# xx_backplane_shield_xi.net
KiCad netlist of a schematic drawn in EAGLE
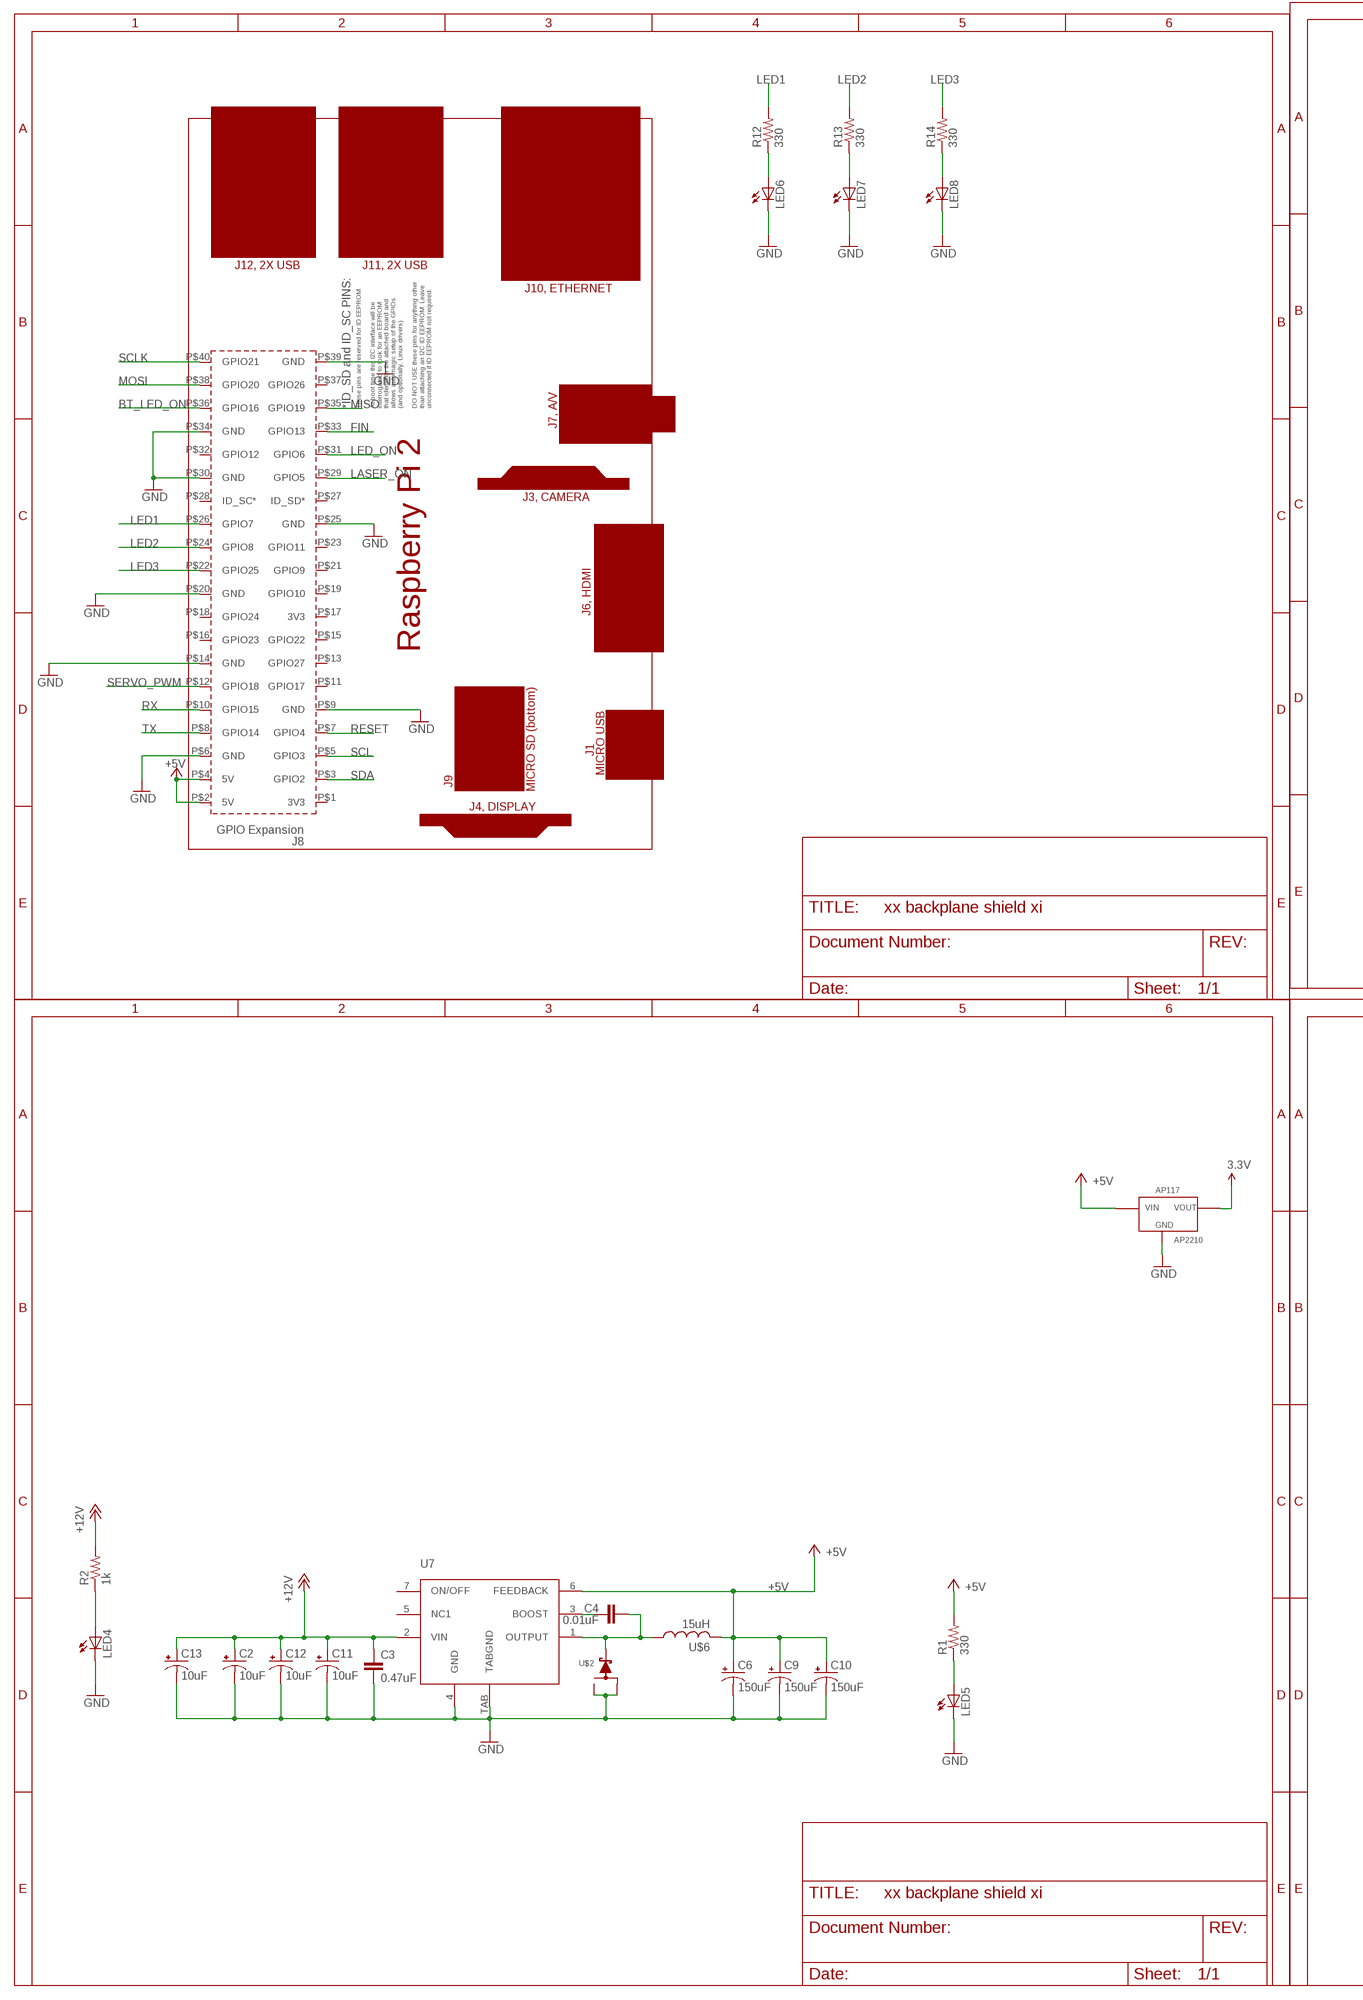
[diagram p0: schematic, sheet 1, part 1 of 2]
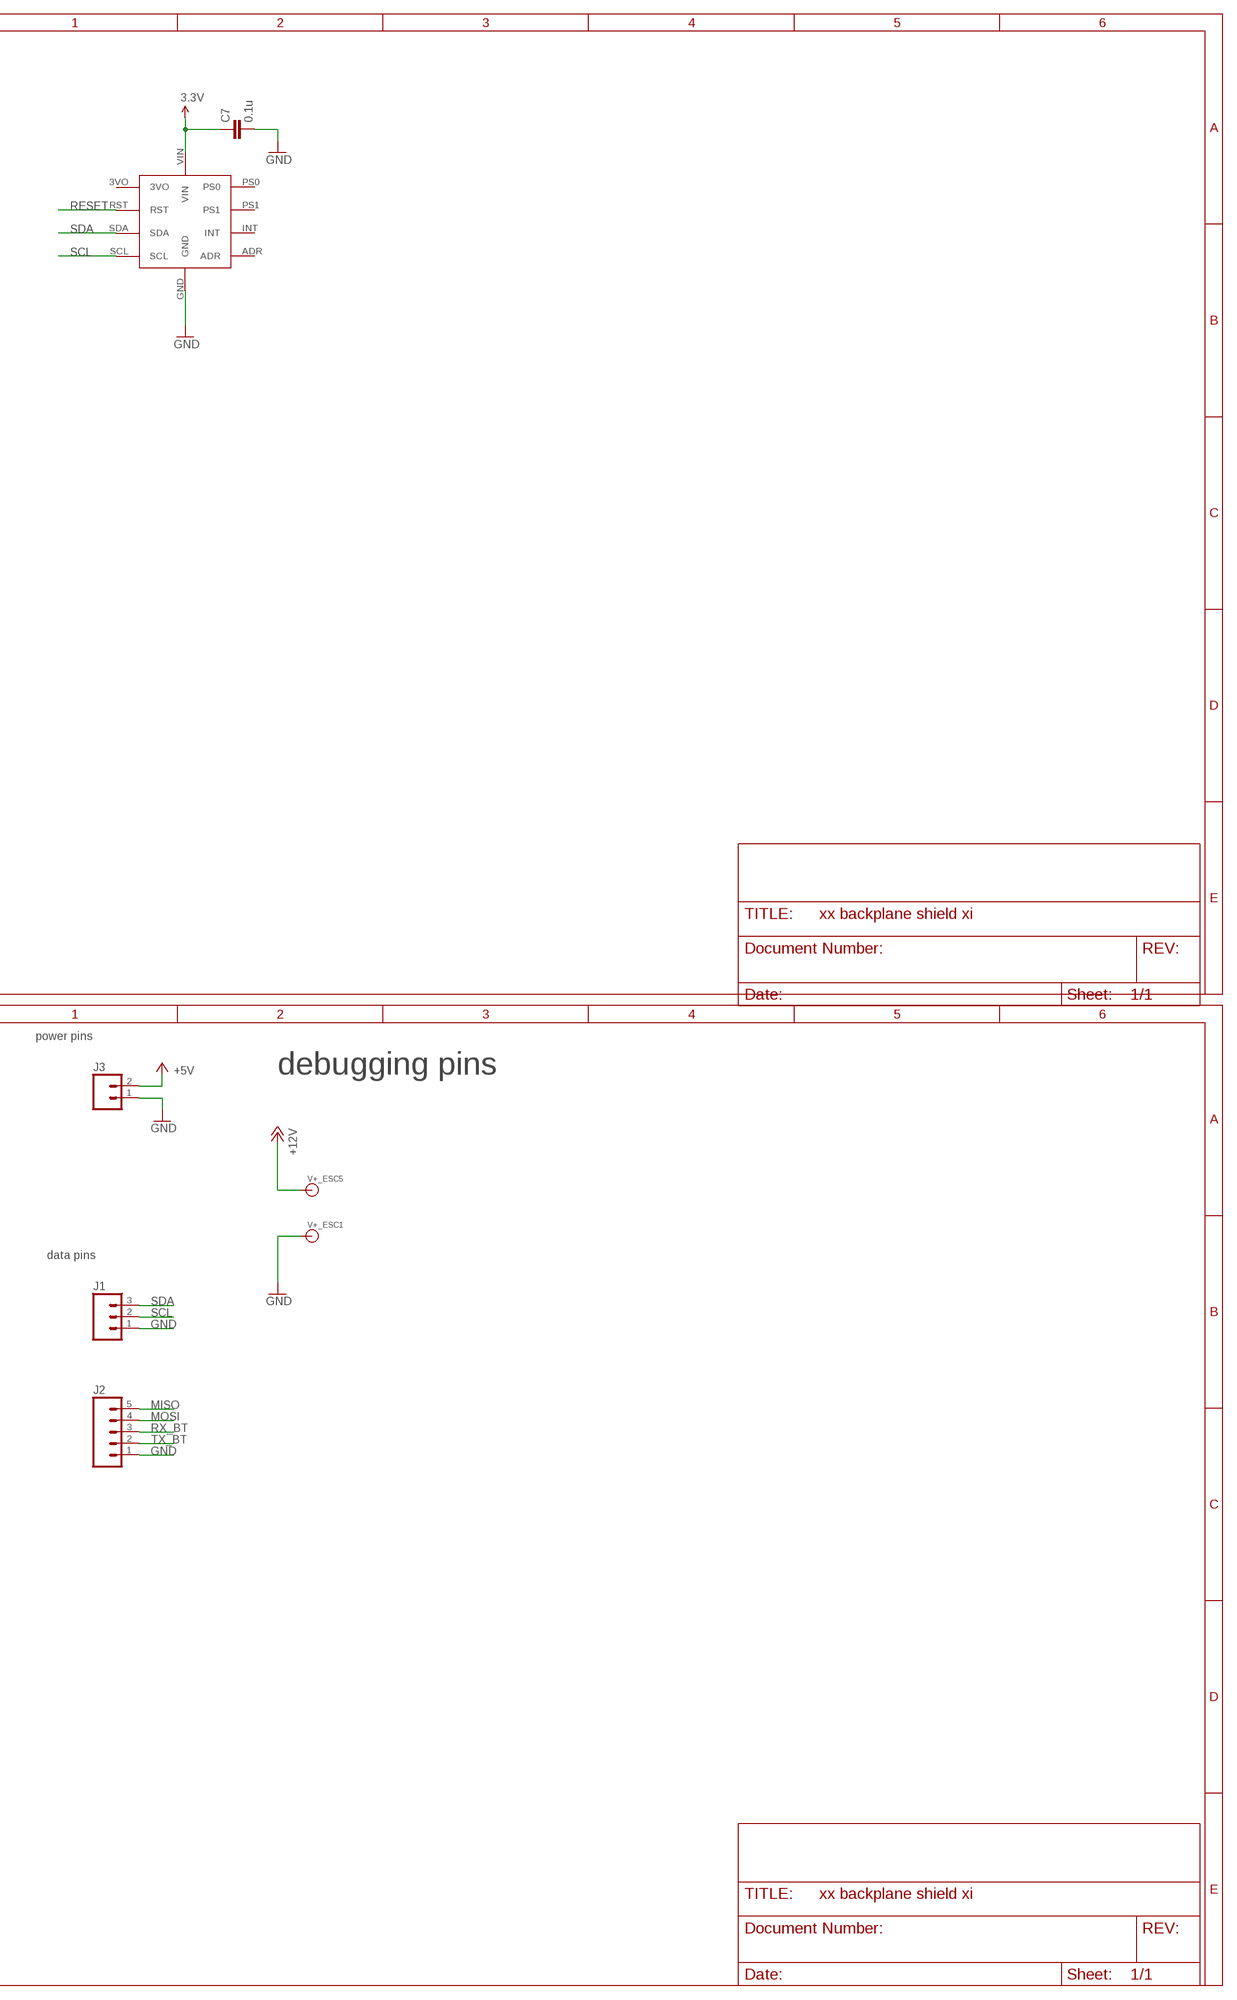
[diagram p1: schematic, sheet 1, part 2 of 2]

(export (version "E")
  (design (tool "Eeschema 10.0.6"))
  (components
    (comp (ref "C2")
      (value "10uF")
      (footprint "eagle-import:CTAN(7.30_4.30MM)")
      (libsource (lib "eagle-import") (part "C-TANTALUM(10UF_150UF)"))
    )
    (comp (ref "C3")
      (value "0.47uF")
      (footprint "eagle-import:0603")
      (libsource (lib "eagle-import") (part "0.18UF-0603-10V-10%"))
    )
    (comp (ref "C4")
      (value "0.01uF")
      (footprint "eagle-import:0603-CAP")
      (libsource (lib "eagle-import") (part "CAP0603-CAP"))
    )
    (comp (ref "C6")
      (value "150uF")
      (footprint "eagle-import:CTAN(7.30_4.30MM)")
      (libsource (lib "eagle-import") (part "C-TANTALUM(10UF_150UF)"))
    )
    (comp (ref "C7")
      (value "0.1u")
      (footprint "eagle-import:0603-CAP")
      (libsource (lib "eagle-import") (part "CAP0603-CAP"))
    )
    (comp (ref "C9")
      (value "150uF")
      (footprint "eagle-import:CTAN(7.30_4.30MM)")
      (libsource (lib "eagle-import") (part "C-TANTALUM(10UF_150UF)"))
    )
    (comp (ref "C10")
      (value "150uF")
      (footprint "eagle-import:CTAN(7.30_4.30MM)")
      (libsource (lib "eagle-import") (part "C-TANTALUM(10UF_150UF)"))
    )
    (comp (ref "C11")
      (value "10uF")
      (footprint "eagle-import:CTAN(7.30_4.30MM)")
      (libsource (lib "eagle-import") (part "C-TANTALUM(10UF_150UF)"))
    )
    (comp (ref "C12")
      (value "10uF")
      (footprint "eagle-import:CTAN(7.30_4.30MM)")
      (libsource (lib "eagle-import") (part "C-TANTALUM(10UF_150UF)"))
    )
    (comp (ref "C13")
      (value "10uF")
      (footprint "eagle-import:CTAN(7.30_4.30MM)")
      (libsource (lib "eagle-import") (part "C-TANTALUM(10UF_150UF)"))
    )
    (comp (ref "J1")
      (value "M03PTH")
      (footprint "eagle-import:1X03")
      (libsource (lib "eagle-import") (part "M03PTH"))
    )
    (comp (ref "J2")
      (value "M05PTH")
      (footprint "eagle-import:1X05")
      (libsource (lib "eagle-import") (part "M05PTH"))
    )
    (comp (ref "J3")
      (value "M02PTH")
      (footprint "eagle-import:1X02")
      (libsource (lib "eagle-import") (part "M02PTH"))
    )
    (comp (ref "LED4")
      (value "LEDSML0603")
      (footprint "eagle-import:SML0603")
      (libsource (lib "eagle-import") (part "LEDSML0603"))
    )
    (comp (ref "LED5")
      (value "LEDSML0603")
      (footprint "eagle-import:SML0603")
      (libsource (lib "eagle-import") (part "LEDSML0603"))
    )
    (comp (ref "LED6")
      (value "LEDSML0603")
      (footprint "eagle-import:SML0603")
      (libsource (lib "eagle-import") (part "LEDSML0603"))
    )
    (comp (ref "LED7")
      (value "LEDSML0603")
      (footprint "eagle-import:SML0603")
      (libsource (lib "eagle-import") (part "LEDSML0603"))
    )
    (comp (ref "LED8")
      (value "LEDSML0603")
      (footprint "eagle-import:SML0603")
      (libsource (lib "eagle-import") (part "LEDSML0603"))
    )
    (comp (ref "PCB1")
      (value "RPI2")
      (footprint "eagle-import:RPI2")
      (libsource (lib "eagle-import") (part "RPI2"))
    )
    (comp (ref "R1")
      (value "330")
      (footprint "eagle-import:R0603")
      (libsource (lib "eagle-import") (part "R-US_R0603"))
    )
    (comp (ref "R2")
      (value "1k")
      (footprint "eagle-import:R0603")
      (libsource (lib "eagle-import") (part "R-US_R0603"))
    )
    (comp (ref "R12")
      (value "330")
      (footprint "eagle-import:R0603")
      (libsource (lib "eagle-import") (part "R-US_R0603"))
    )
    (comp (ref "R13")
      (value "330")
      (footprint "eagle-import:R0603")
      (libsource (lib "eagle-import") (part "R-US_R0603"))
    )
    (comp (ref "R14")
      (value "330")
      (footprint "eagle-import:R0603")
      (libsource (lib "eagle-import") (part "R-US_R0603"))
    )
    (comp (ref "U$2")
      (value "SWITCHMODE_SCHOTTKY")
      (footprint "eagle-import:DPAK-3")
      (libsource (lib "eagle-import") (part "SWITCHMODE_SCHOTTKY"))
    )
    (comp (ref "U$3")
      (value "BNO055_9DOF_BREAKOUT")
      (footprint "eagle-import:BNO055")
      (libsource (lib "eagle-import") (part "BNO055_9DOF_BREAKOUT"))
    )
    (comp (ref "U$5")
      (value "AP2210")
      (footprint "eagle-import:SOT-23-3")
      (libsource (lib "eagle-import") (part "AP2210"))
    )
    (comp (ref "U$6")
      (value "15uH")
      (footprint "eagle-import:HCMA1305")
      (libsource (lib "eagle-import") (part "HCMA1305"))
    )
    (comp (ref "U7")
      (value "LM2678")
      (footprint "eagle-import:LM2678")
      (libsource (lib "eagle-import") (part "LM2678"))
    )
    (comp (ref "V+_ESC1")
      (value "BANANA_CONN")
      (footprint "eagle-import:BANANA_CONN")
      (libsource (lib "eagle-import") (part "BANANA_CONN"))
    )
    (comp (ref "V+_ESC5")
      (value "BANANA_CONN")
      (footprint "eagle-import:BANANA_CONN")
      (libsource (lib "eagle-import") (part "BANANA_CONN"))
    )
  )
  (nets
    (net (code "1") (name "+5V") (class "Default")
      (node (ref "C10") (pin "+") (pinfunction "+_+") (pintype "passive"))
      (node (ref "C6") (pin "+") (pinfunction "+_+") (pintype "passive"))
      (node (ref "C9") (pin "+") (pinfunction "+_+") (pintype "passive"))
      (node (ref "J3") (pin "2") (pinfunction "2_2") (pintype "passive"))
      (node (ref "PCB1") (pin "P$2") (pinfunction "5V_P$2") (pintype "bidirectional"))
      (node (ref "PCB1") (pin "P$4") (pinfunction "5V_P$4") (pintype "bidirectional"))
      (node (ref "R1") (pin "2") (pinfunction "2_2") (pintype "passive"))
      (node (ref "U$5") (pin "VIN") (pinfunction "VIN_VIN") (pintype "input"))
      (node (ref "U$6") (pin "P$2") (pinfunction "2_P$2") (pintype "passive"))
      (node (ref "U7") (pin "6") (pinfunction "FEEDBACK_6") (pintype "bidirectional"))
    )
    (net (code "2") (name "+12V") (class "Default")
      (node (ref "C11") (pin "+") (pinfunction "+_+") (pintype "passive"))
      (node (ref "C12") (pin "+") (pinfunction "+_+") (pintype "passive"))
      (node (ref "C13") (pin "+") (pinfunction "+_+") (pintype "passive"))
      (node (ref "C2") (pin "+") (pinfunction "+_+") (pintype "passive"))
      (node (ref "C3") (pin "1") (pinfunction "1_1") (pintype "passive"))
      (node (ref "R2") (pin "2") (pinfunction "2_2") (pintype "passive"))
      (node (ref "U7") (pin "2") (pinfunction "VIN_2") (pintype "bidirectional"))
      (node (ref "V+_ESC5") (pin "P$1") (pinfunction "1_P$1") (pintype "passive"))
    )
    (net (code "3") (name "/BT_LED_ON") (class "Default")
      (node (ref "PCB1") (pin "P$36") (pinfunction "GPIO16_P$36") (pintype "bidirectional"))
    )
    (net (code "4") (name "/FIN") (class "Default")
      (node (ref "PCB1") (pin "P$33") (pinfunction "GPIO13_P$33") (pintype "bidirectional"))
    )
    (net (code "5") (name "/LASER_ON") (class "Default")
      (node (ref "PCB1") (pin "P$29") (pinfunction "GPIO5_P$29") (pintype "bidirectional"))
    )
    (net (code "6") (name "/LED1") (class "Default")
      (node (ref "PCB1") (pin "P$26") (pinfunction "GPIO7_P$26") (pintype "bidirectional"))
      (node (ref "R12") (pin "2") (pinfunction "2_2") (pintype "passive"))
    )
    (net (code "7") (name "/LED2") (class "Default")
      (node (ref "PCB1") (pin "P$24") (pinfunction "GPIO8_P$24") (pintype "bidirectional"))
      (node (ref "R13") (pin "2") (pinfunction "2_2") (pintype "passive"))
    )
    (net (code "8") (name "/LED3") (class "Default")
      (node (ref "PCB1") (pin "P$22") (pinfunction "GPIO25_P$22") (pintype "bidirectional"))
      (node (ref "R14") (pin "2") (pinfunction "2_2") (pintype "passive"))
    )
    (net (code "9") (name "/LED_ON") (class "Default")
      (node (ref "PCB1") (pin "P$31") (pinfunction "GPIO6_P$31") (pintype "bidirectional"))
    )
    (net (code "10") (name "/MISO") (class "Default")
      (node (ref "J2") (pin "5") (pinfunction "5_5") (pintype "passive"))
      (node (ref "PCB1") (pin "P$35") (pinfunction "GPIO19_P$35") (pintype "bidirectional"))
    )
    (net (code "11") (name "/MOSI") (class "Default")
      (node (ref "J2") (pin "4") (pinfunction "4_4") (pintype "passive"))
      (node (ref "PCB1") (pin "P$38") (pinfunction "GPIO20_P$38") (pintype "bidirectional"))
    )
    (net (code "12") (name "/RESET") (class "Default")
      (node (ref "PCB1") (pin "P$7") (pinfunction "GPIO4_P$7") (pintype "bidirectional"))
      (node (ref "U$3") (pin "RST") (pinfunction "RST_RST") (pintype "bidirectional"))
    )
    (net (code "13") (name "/RX") (class "Default")
      (node (ref "PCB1") (pin "P$10") (pinfunction "GPIO15_P$10") (pintype "bidirectional"))
    )
    (net (code "14") (name "/RX_BT") (class "Default")
      (node (ref "J2") (pin "3") (pinfunction "3_3") (pintype "passive"))
    )
    (net (code "15") (name "/SCL") (class "Default")
      (node (ref "J1") (pin "2") (pinfunction "2_2") (pintype "passive"))
      (node (ref "PCB1") (pin "P$5") (pinfunction "GPIO3_P$5") (pintype "bidirectional"))
      (node (ref "U$3") (pin "SCL") (pinfunction "SCL_SCL") (pintype "bidirectional"))
    )
    (net (code "16") (name "/SCLK") (class "Default")
      (node (ref "PCB1") (pin "P$40") (pinfunction "GPIO21_P$40") (pintype "bidirectional"))
    )
    (net (code "17") (name "/SDA") (class "Default")
      (node (ref "J1") (pin "3") (pinfunction "3_3") (pintype "passive"))
      (node (ref "PCB1") (pin "P$3") (pinfunction "GPIO2_P$3") (pintype "bidirectional"))
      (node (ref "U$3") (pin "SDA") (pinfunction "SDA_SDA") (pintype "bidirectional"))
    )
    (net (code "18") (name "/SERVO_PWM") (class "Default")
      (node (ref "PCB1") (pin "P$12") (pinfunction "GPIO18_P$12") (pintype "bidirectional"))
    )
    (net (code "19") (name "/TX") (class "Default")
      (node (ref "PCB1") (pin "P$8") (pinfunction "GPIO14_P$8") (pintype "bidirectional"))
    )
    (net (code "20") (name "/TX_BT") (class "Default")
      (node (ref "J2") (pin "2") (pinfunction "2_2") (pintype "passive"))
    )
    (net (code "21") (name "3.3V") (class "Default")
      (node (ref "C7") (pin "1") (pinfunction "1_1") (pintype "passive"))
      (node (ref "U$3") (pin "VIN") (pinfunction "VIN_VIN") (pintype "bidirectional"))
      (node (ref "U$5") (pin "VOUT") (pinfunction "VOUT_VOUT") (pintype "output"))
    )
    (net (code "22") (name "GND") (class "Default")
      (node (ref "C10") (pin "-") (pinfunction "-_-") (pintype "passive"))
      (node (ref "C11") (pin "-") (pinfunction "-_-") (pintype "passive"))
      (node (ref "C12") (pin "-") (pinfunction "-_-") (pintype "passive"))
      (node (ref "C13") (pin "-") (pinfunction "-_-") (pintype "passive"))
      (node (ref "C2") (pin "-") (pinfunction "-_-") (pintype "passive"))
      (node (ref "C3") (pin "2") (pinfunction "2_2") (pintype "passive"))
      (node (ref "C6") (pin "-") (pinfunction "-_-") (pintype "passive"))
      (node (ref "C7") (pin "2") (pinfunction "2_2") (pintype "passive"))
      (node (ref "C9") (pin "-") (pinfunction "-_-") (pintype "passive"))
      (node (ref "J1") (pin "1") (pinfunction "1_1") (pintype "passive"))
      (node (ref "J2") (pin "1") (pinfunction "1_1") (pintype "passive"))
      (node (ref "J3") (pin "1") (pinfunction "1_1") (pintype "passive"))
      (node (ref "LED4") (pin "C") (pinfunction "C_C") (pintype "passive"))
      (node (ref "LED5") (pin "C") (pinfunction "C_C") (pintype "passive"))
      (node (ref "LED6") (pin "C") (pinfunction "C_C") (pintype "passive"))
      (node (ref "LED7") (pin "C") (pinfunction "C_C") (pintype "passive"))
      (node (ref "LED8") (pin "C") (pinfunction "C_C") (pintype "passive"))
      (node (ref "PCB1") (pin "P$14") (pinfunction "GND_P$14") (pintype "bidirectional"))
      (node (ref "PCB1") (pin "P$20") (pinfunction "GND_P$20") (pintype "bidirectional"))
      (node (ref "PCB1") (pin "P$25") (pinfunction "GND_P$25") (pintype "bidirectional"))
      (node (ref "PCB1") (pin "P$30") (pinfunction "GND_P$30") (pintype "bidirectional"))
      (node (ref "PCB1") (pin "P$34") (pinfunction "GND_P$34") (pintype "bidirectional"))
      (node (ref "PCB1") (pin "P$39") (pinfunction "GND_P$39") (pintype "bidirectional"))
      (node (ref "PCB1") (pin "P$6") (pinfunction "GND_P$6") (pintype "bidirectional"))
      (node (ref "PCB1") (pin "P$9") (pinfunction "GND_P$9") (pintype "bidirectional"))
      (node (ref "U$2") (pin "P$1") (pinfunction "P$1_P$1") (pintype "bidirectional"))
      (node (ref "U$2") (pin "P$3") (pinfunction "P$3_P$3") (pintype "bidirectional"))
      (node (ref "U$3") (pin "GND") (pinfunction "GND_GND") (pintype "bidirectional"))
      (node (ref "U$5") (pin "GND") (pinfunction "GND_GND") (pintype "bidirectional"))
      (node (ref "U7") (pin "4") (pinfunction "GND_4") (pintype "bidirectional"))
      (node (ref "U7") (pin "TAB") (pinfunction "TABGND_TAB") (pintype "bidirectional"))
      (node (ref "V+_ESC1") (pin "P$1") (pinfunction "1_P$1") (pintype "passive"))
    )
    (net (code "23") (name "Net-(LED4-PadA)") (class "Default")
      (node (ref "LED4") (pin "A") (pinfunction "A_A") (pintype "passive"))
      (node (ref "R2") (pin "1") (pinfunction "1_1") (pintype "passive"))
    )
    (net (code "24") (name "Net-(LED5-PadA)") (class "Default")
      (node (ref "LED5") (pin "A") (pinfunction "A_A") (pintype "passive"))
      (node (ref "R1") (pin "1") (pinfunction "1_1") (pintype "passive"))
    )
    (net (code "25") (name "Net-(LED6-PadA)") (class "Default")
      (node (ref "LED6") (pin "A") (pinfunction "A_A") (pintype "passive"))
      (node (ref "R12") (pin "1") (pinfunction "1_1") (pintype "passive"))
    )
    (net (code "26") (name "Net-(LED7-PadA)") (class "Default")
      (node (ref "LED7") (pin "A") (pinfunction "A_A") (pintype "passive"))
      (node (ref "R13") (pin "1") (pinfunction "1_1") (pintype "passive"))
    )
    (net (code "27") (name "Net-(LED8-PadA)") (class "Default")
      (node (ref "LED8") (pin "A") (pinfunction "A_A") (pintype "passive"))
      (node (ref "R14") (pin "1") (pinfunction "1_1") (pintype "passive"))
    )
    (net (code "28") (name "Net-(U$6-1)") (class "Default")
      (node (ref "C4") (pin "2") (pinfunction "2_2") (pintype "passive"))
      (node (ref "U$2") (pin "P$4") (pinfunction "P$4_P$4") (pintype "bidirectional"))
      (node (ref "U$6") (pin "P$1") (pinfunction "1_P$1") (pintype "passive"))
      (node (ref "U7") (pin "1") (pinfunction "OUTPUT_1") (pintype "bidirectional"))
    )
    (net (code "29") (name "Net-(U7-BOOST)") (class "Default")
      (node (ref "C4") (pin "1") (pinfunction "1_1") (pintype "passive"))
      (node (ref "U7") (pin "3") (pinfunction "BOOST_3") (pintype "bidirectional"))
    )
    (net (code "30") (name "unconnected-(PCB1-3V3-PadP$1)") (class "Default")
      (node (ref "PCB1") (pin "P$1") (pinfunction "3V3_P$1") (pintype "bidirectional"))
    )
    (net (code "31") (name "unconnected-(PCB1-3V3-PadP$17)") (class "Default")
      (node (ref "PCB1") (pin "P$17") (pinfunction "3V3_P$17") (pintype "bidirectional"))
    )
    (net (code "32") (name "unconnected-(PCB1-GPIO9-PadP$21)") (class "Default")
      (node (ref "PCB1") (pin "P$21") (pinfunction "GPIO9_P$21") (pintype "bidirectional"))
    )
    (net (code "33") (name "unconnected-(PCB1-GPIO10-PadP$19)") (class "Default")
      (node (ref "PCB1") (pin "P$19") (pinfunction "GPIO10_P$19") (pintype "bidirectional"))
    )
    (net (code "34") (name "unconnected-(PCB1-GPIO11-PadP$23)") (class "Default")
      (node (ref "PCB1") (pin "P$23") (pinfunction "GPIO11_P$23") (pintype "bidirectional"))
    )
    (net (code "35") (name "unconnected-(PCB1-GPIO12-PadP$32)") (class "Default")
      (node (ref "PCB1") (pin "P$32") (pinfunction "GPIO12_P$32") (pintype "bidirectional"))
    )
    (net (code "36") (name "unconnected-(PCB1-GPIO17-PadP$11)") (class "Default")
      (node (ref "PCB1") (pin "P$11") (pinfunction "GPIO17_P$11") (pintype "bidirectional"))
    )
    (net (code "37") (name "unconnected-(PCB1-GPIO22-PadP$15)") (class "Default")
      (node (ref "PCB1") (pin "P$15") (pinfunction "GPIO22_P$15") (pintype "bidirectional"))
    )
    (net (code "38") (name "unconnected-(PCB1-GPIO23-PadP$16)") (class "Default")
      (node (ref "PCB1") (pin "P$16") (pinfunction "GPIO23_P$16") (pintype "bidirectional"))
    )
    (net (code "39") (name "unconnected-(PCB1-GPIO24-PadP$18)") (class "Default")
      (node (ref "PCB1") (pin "P$18") (pinfunction "GPIO24_P$18") (pintype "bidirectional"))
    )
    (net (code "40") (name "unconnected-(PCB1-GPIO26-PadP$37)") (class "Default")
      (node (ref "PCB1") (pin "P$37") (pinfunction "GPIO26_P$37") (pintype "bidirectional"))
    )
    (net (code "41") (name "unconnected-(PCB1-GPIO27-PadP$13)") (class "Default")
      (node (ref "PCB1") (pin "P$13") (pinfunction "GPIO27_P$13") (pintype "bidirectional"))
    )
    (net (code "42") (name "unconnected-(PCB1-ID_SC*-PadP$28)") (class "Default")
      (node (ref "PCB1") (pin "P$28") (pinfunction "ID_SC*_P$28") (pintype "bidirectional"))
    )
    (net (code "43") (name "unconnected-(PCB1-ID_SD*-PadP$27)") (class "Default")
      (node (ref "PCB1") (pin "P$27") (pinfunction "ID_SD*_P$27") (pintype "bidirectional"))
    )
    (net (code "44") (name "unconnected-(U$3-Pad3VO)") (class "Default")
      (node (ref "U$3") (pin "3VO") (pinfunction "3VO_3VO") (pintype "bidirectional"))
    )
    (net (code "45") (name "unconnected-(U$3-PadADR)") (class "Default")
      (node (ref "U$3") (pin "ADR") (pinfunction "ADR_ADR") (pintype "bidirectional"))
    )
    (net (code "46") (name "unconnected-(U$3-PadINT)") (class "Default")
      (node (ref "U$3") (pin "INT") (pinfunction "INT_INT") (pintype "bidirectional"))
    )
    (net (code "47") (name "unconnected-(U$3-PadPS0)") (class "Default")
      (node (ref "U$3") (pin "PS0") (pinfunction "PS0_PS0") (pintype "bidirectional"))
    )
    (net (code "48") (name "unconnected-(U$3-PadPS1)") (class "Default")
      (node (ref "U$3") (pin "PS1") (pinfunction "PS1_PS1") (pintype "bidirectional"))
    )
    (net (code "49") (name "unconnected-(U7-NC1-Pad5)") (class "Default")
      (node (ref "U7") (pin "5") (pinfunction "NC1_5") (pintype "no_connect"))
    )
    (net (code "50") (name "unconnected-(U7-ON{slash}OFF-Pad7)") (class "Default")
      (node (ref "U7") (pin "7") (pinfunction "ON/OFF_7") (pintype "bidirectional"))
    )
  )
)
